# Looping_Louie_Motherboard.net
KiCad netlist of a schematic drawn in EAGLE
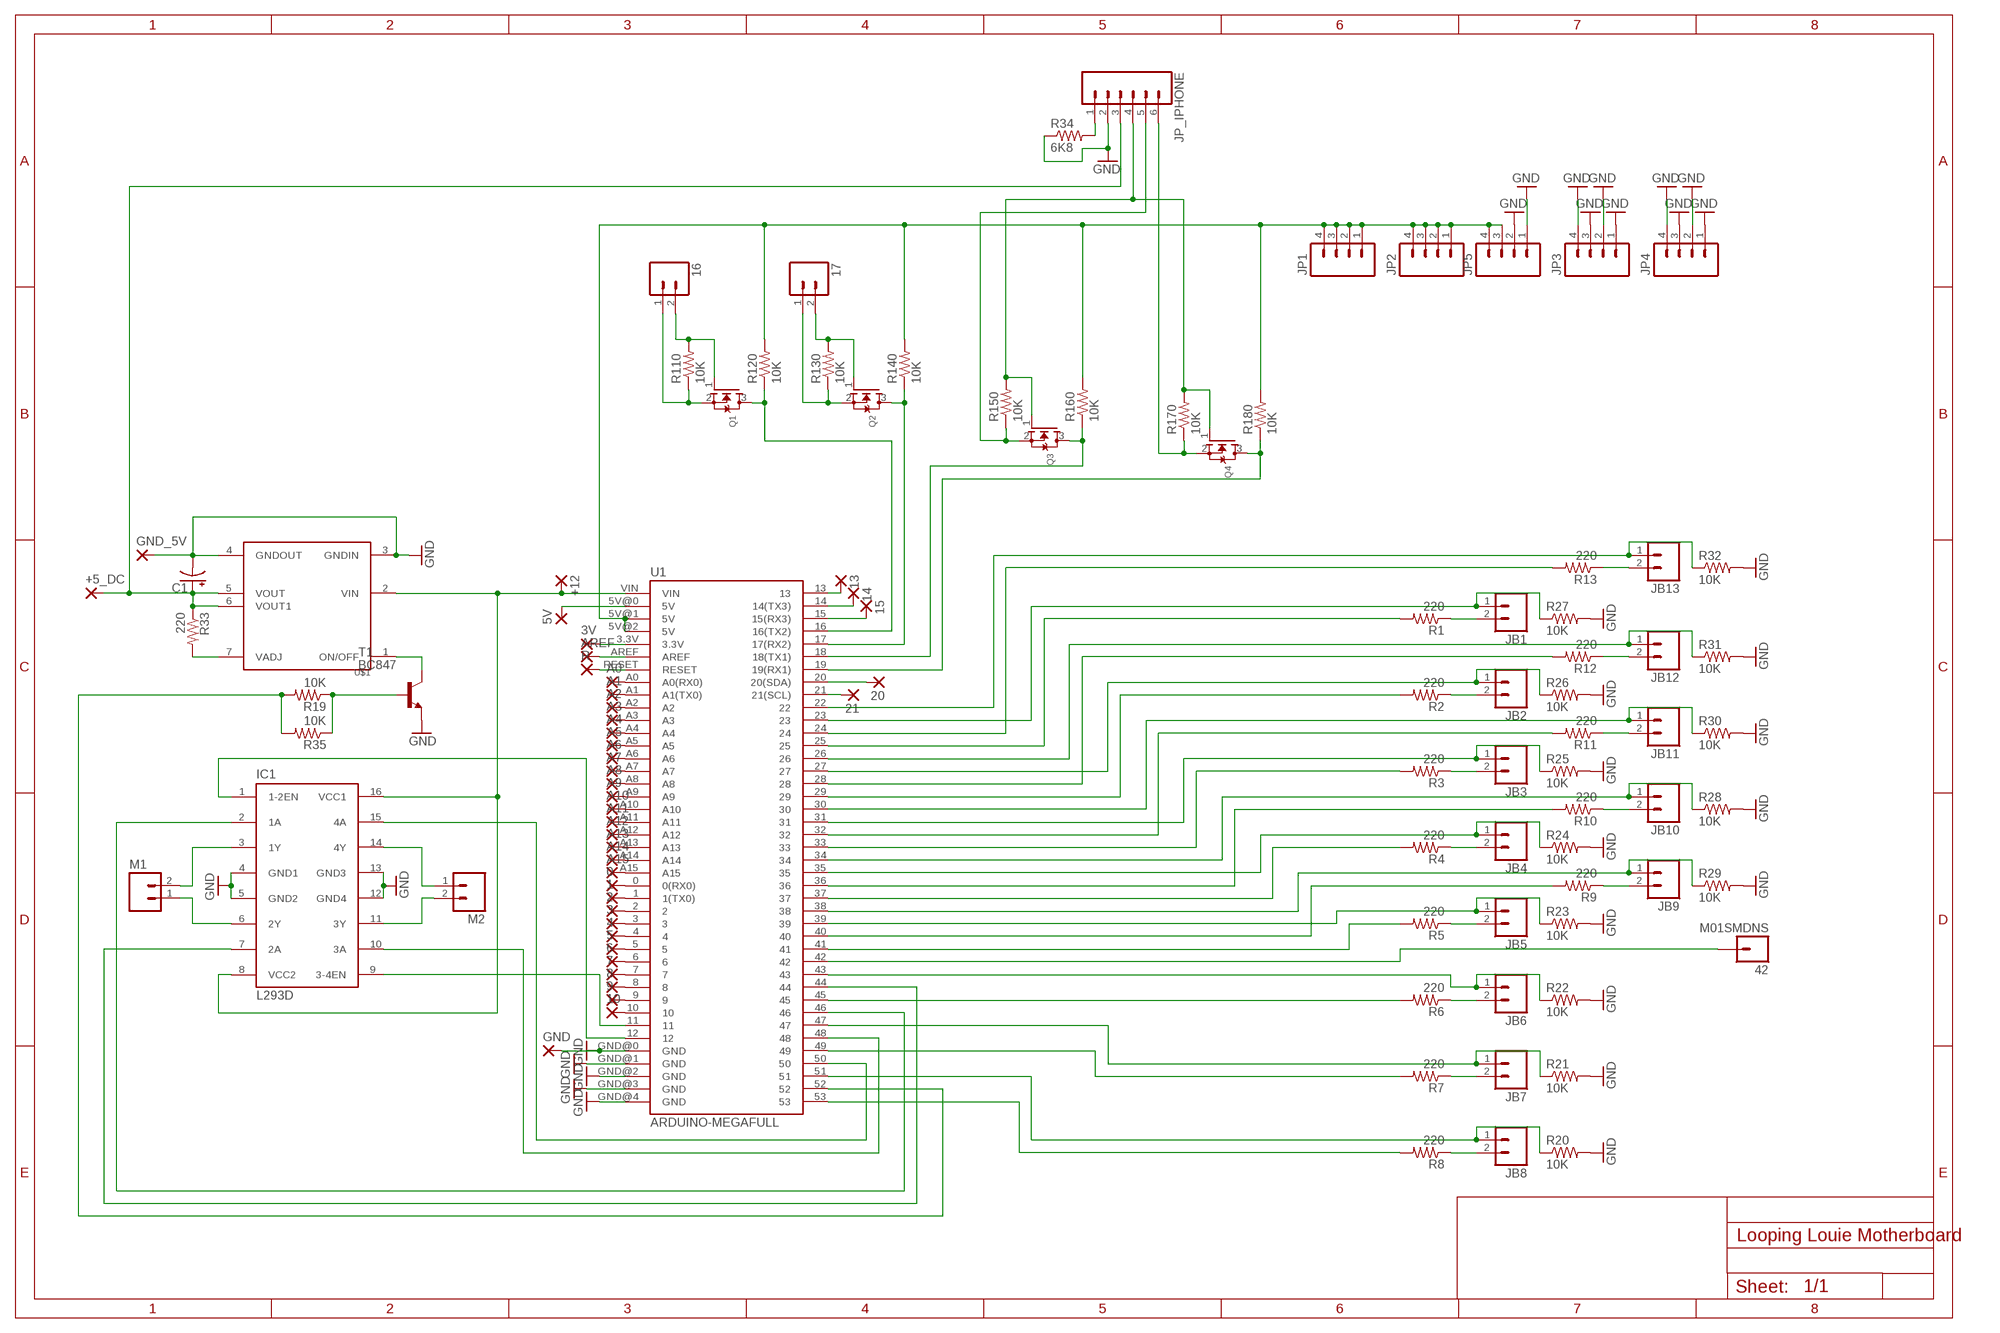
[diagram p0: schematic, sheet 1]

(export (version "E")
  (design (tool "Eeschema 10.0.6"))
  (components
    (comp (ref "+5_DC")
      (value "3,81/1,4")
      (footprint "eagle-import:3,81_1,4")
      (libsource (lib "eagle-import") (part "3,81/1,4"))
    )
    (comp (ref "+12")
      (value "3,81/1,4")
      (footprint "eagle-import:3,81_1,4")
      (libsource (lib "eagle-import") (part "3,81/1,4"))
    )
    (comp (ref "0")
      (value "1,6/0,8")
      (footprint "eagle-import:1,6_0,8")
      (libsource (lib "eagle-import") (part "1,6/0,8"))
    )
    (comp (ref "1")
      (value "1,6/0,8")
      (footprint "eagle-import:1,6_0,8")
      (libsource (lib "eagle-import") (part "1,6/0,8"))
    )
    (comp (ref "2")
      (value "1,6/0,8")
      (footprint "eagle-import:1,6_0,8")
      (libsource (lib "eagle-import") (part "1,6/0,8"))
    )
    (comp (ref "3")
      (value "1,6/0,8")
      (footprint "eagle-import:1,6_0,8")
      (libsource (lib "eagle-import") (part "1,6/0,8"))
    )
    (comp (ref "3V")
      (value "1,6/0,8")
      (footprint "eagle-import:1,6_0,8")
      (libsource (lib "eagle-import") (part "1,6/0,8"))
    )
    (comp (ref "4")
      (value "1,6/0,8")
      (footprint "eagle-import:1,6_0,8")
      (libsource (lib "eagle-import") (part "1,6/0,8"))
    )
    (comp (ref "5")
      (value "1,6/0,8")
      (footprint "eagle-import:1,6_0,8")
      (libsource (lib "eagle-import") (part "1,6/0,8"))
    )
    (comp (ref "5V")
      (value "1,6/0,8")
      (footprint "eagle-import:1,6_0,8")
      (libsource (lib "eagle-import") (part "1,6/0,8"))
    )
    (comp (ref "6")
      (value "1,6/0,8")
      (footprint "eagle-import:1,6_0,8")
      (libsource (lib "eagle-import") (part "1,6/0,8"))
    )
    (comp (ref "7")
      (value "1,6/0,8")
      (footprint "eagle-import:1,6_0,8")
      (libsource (lib "eagle-import") (part "1,6/0,8"))
    )
    (comp (ref "8")
      (value "1,6/0,8")
      (footprint "eagle-import:1,6_0,8")
      (libsource (lib "eagle-import") (part "1,6/0,8"))
    )
    (comp (ref "9")
      (value "1,6/0,8")
      (footprint "eagle-import:1,6_0,8")
      (libsource (lib "eagle-import") (part "1,6/0,8"))
    )
    (comp (ref "10")
      (value "1,6/0,8")
      (footprint "eagle-import:1,6_0,8")
      (libsource (lib "eagle-import") (part "1,6/0,8"))
    )
    (comp (ref "13")
      (value "1,6/0,8")
      (footprint "eagle-import:1,6_0,8")
      (libsource (lib "eagle-import") (part "1,6/0,8"))
    )
    (comp (ref "14")
      (value "1,6/0,8")
      (footprint "eagle-import:1,6_0,8")
      (libsource (lib "eagle-import") (part "1,6/0,8"))
    )
    (comp (ref "15")
      (value "1,6/0,8")
      (footprint "eagle-import:1,6_0,8")
      (libsource (lib "eagle-import") (part "1,6/0,8"))
    )
    (comp (ref "16")
      (value "M021X02_NO_SILK")
      (footprint "eagle-import:1X02_NO_SILK")
      (libsource (lib "eagle-import") (part "M021X02_NO_SILK"))
    )
    (comp (ref "17")
      (value "M021X02_NO_SILK")
      (footprint "eagle-import:1X02_NO_SILK")
      (libsource (lib "eagle-import") (part "M021X02_NO_SILK"))
    )
    (comp (ref "20")
      (value "1,6/0,8")
      (footprint "eagle-import:1,6_0,8")
      (libsource (lib "eagle-import") (part "1,6/0,8"))
    )
    (comp (ref "21")
      (value "1,6/0,8")
      (footprint "eagle-import:1,6_0,8")
      (libsource (lib "eagle-import") (part "1,6/0,8"))
    )
    (comp (ref "42")
      (value "M01SMDNS")
      (footprint "eagle-import:1X01NS")
      (libsource (lib "eagle-import") (part "M01SMDNS"))
    )
    (comp (ref "A0")
      (value "1,6/0,8")
      (footprint "eagle-import:1,6_0,8")
      (libsource (lib "eagle-import") (part "1,6/0,8"))
    )
    (comp (ref "A1")
      (value "1,6/0,8")
      (footprint "eagle-import:1,6_0,8")
      (libsource (lib "eagle-import") (part "1,6/0,8"))
    )
    (comp (ref "A2")
      (value "1,6/0,8")
      (footprint "eagle-import:1,6_0,8")
      (libsource (lib "eagle-import") (part "1,6/0,8"))
    )
    (comp (ref "A3")
      (value "1,6/0,8")
      (footprint "eagle-import:1,6_0,8")
      (libsource (lib "eagle-import") (part "1,6/0,8"))
    )
    (comp (ref "A4")
      (value "1,6/0,8")
      (footprint "eagle-import:1,6_0,8")
      (libsource (lib "eagle-import") (part "1,6/0,8"))
    )
    (comp (ref "A5")
      (value "1,6/0,8")
      (footprint "eagle-import:1,6_0,8")
      (libsource (lib "eagle-import") (part "1,6/0,8"))
    )
    (comp (ref "A6")
      (value "1,6/0,8")
      (footprint "eagle-import:1,6_0,8")
      (libsource (lib "eagle-import") (part "1,6/0,8"))
    )
    (comp (ref "A7")
      (value "1,6/0,8")
      (footprint "eagle-import:1,6_0,8")
      (libsource (lib "eagle-import") (part "1,6/0,8"))
    )
    (comp (ref "A8")
      (value "1,6/0,8")
      (footprint "eagle-import:1,6_0,8")
      (libsource (lib "eagle-import") (part "1,6/0,8"))
    )
    (comp (ref "A9")
      (value "1,6/0,8")
      (footprint "eagle-import:1,6_0,8")
      (libsource (lib "eagle-import") (part "1,6/0,8"))
    )
    (comp (ref "A10")
      (value "1,6/0,8")
      (footprint "eagle-import:1,6_0,8")
      (libsource (lib "eagle-import") (part "1,6/0,8"))
    )
    (comp (ref "A11")
      (value "1,6/0,8")
      (footprint "eagle-import:1,6_0,8")
      (libsource (lib "eagle-import") (part "1,6/0,8"))
    )
    (comp (ref "A12")
      (value "1,6/0,8")
      (footprint "eagle-import:1,6_0,8")
      (libsource (lib "eagle-import") (part "1,6/0,8"))
    )
    (comp (ref "A13")
      (value "1,6/0,8")
      (footprint "eagle-import:1,6_0,8")
      (libsource (lib "eagle-import") (part "1,6/0,8"))
    )
    (comp (ref "A14")
      (value "1,6/0,8")
      (footprint "eagle-import:1,6_0,8")
      (libsource (lib "eagle-import") (part "1,6/0,8"))
    )
    (comp (ref "A15")
      (value "1,6/0,8")
      (footprint "eagle-import:1,6_0,8")
      (libsource (lib "eagle-import") (part "1,6/0,8"))
    )
    (comp (ref "AREF")
      (value "1,6/0,8")
      (footprint "eagle-import:1,6_0,8")
      (libsource (lib "eagle-import") (part "1,6/0,8"))
    )
    (comp (ref "C1")
      (value "CAP_POLG")
      (footprint "eagle-import:PANASONIC_G")
      (libsource (lib "eagle-import") (part "CAP_POLG"))
    )
    (comp (ref "GND")
      (value "3,81/1,4")
      (footprint "eagle-import:3,81_1,4")
      (libsource (lib "eagle-import") (part "3,81/1,4"))
    )
    (comp (ref "GND_5V")
      (value "3,81/1,4")
      (footprint "eagle-import:3,81_1,4")
      (libsource (lib "eagle-import") (part "3,81/1,4"))
    )
    (comp (ref "IC1")
      (value "L293D")
      (footprint "eagle-import:DIL16")
      (libsource (lib "eagle-import") (part "L293D"))
    )
    (comp (ref "JB1")
      (value "M021X02_NO_SILK")
      (footprint "eagle-import:1X02_NO_SILK")
      (libsource (lib "eagle-import") (part "M021X02_NO_SILK"))
    )
    (comp (ref "JB2")
      (value "M021X02_NO_SILK")
      (footprint "eagle-import:1X02_NO_SILK")
      (libsource (lib "eagle-import") (part "M021X02_NO_SILK"))
    )
    (comp (ref "JB3")
      (value "M021X02_NO_SILK")
      (footprint "eagle-import:1X02_NO_SILK")
      (libsource (lib "eagle-import") (part "M021X02_NO_SILK"))
    )
    (comp (ref "JB4")
      (value "M021X02_NO_SILK")
      (footprint "eagle-import:1X02_NO_SILK")
      (libsource (lib "eagle-import") (part "M021X02_NO_SILK"))
    )
    (comp (ref "JB5")
      (value "M021X02_NO_SILK")
      (footprint "eagle-import:1X02_NO_SILK")
      (libsource (lib "eagle-import") (part "M021X02_NO_SILK"))
    )
    (comp (ref "JB6")
      (value "M021X02_NO_SILK")
      (footprint "eagle-import:1X02_NO_SILK")
      (libsource (lib "eagle-import") (part "M021X02_NO_SILK"))
    )
    (comp (ref "JB7")
      (value "M021X02_NO_SILK")
      (footprint "eagle-import:1X02_NO_SILK")
      (libsource (lib "eagle-import") (part "M021X02_NO_SILK"))
    )
    (comp (ref "JB8")
      (value "M021X02_NO_SILK")
      (footprint "eagle-import:1X02_NO_SILK")
      (libsource (lib "eagle-import") (part "M021X02_NO_SILK"))
    )
    (comp (ref "JB9")
      (value "M021X02_NO_SILK")
      (footprint "eagle-import:1X02_NO_SILK")
      (libsource (lib "eagle-import") (part "M021X02_NO_SILK"))
    )
    (comp (ref "JB10")
      (value "M021X02_NO_SILK")
      (footprint "eagle-import:1X02_NO_SILK")
      (libsource (lib "eagle-import") (part "M021X02_NO_SILK"))
    )
    (comp (ref "JB11")
      (value "M021X02_NO_SILK")
      (footprint "eagle-import:1X02_NO_SILK")
      (libsource (lib "eagle-import") (part "M021X02_NO_SILK"))
    )
    (comp (ref "JB12")
      (value "M021X02_NO_SILK")
      (footprint "eagle-import:1X02_NO_SILK")
      (libsource (lib "eagle-import") (part "M021X02_NO_SILK"))
    )
    (comp (ref "JB13")
      (value "M021X02_NO_SILK")
      (footprint "eagle-import:1X02_NO_SILK")
      (libsource (lib "eagle-import") (part "M021X02_NO_SILK"))
    )
    (comp (ref "JP1")
      (value "M041X04_NO_SILK")
      (footprint "eagle-import:1X04_NO_SILK")
      (libsource (lib "eagle-import") (part "M041X04_NO_SILK"))
    )
    (comp (ref "JP2")
      (value "M041X04_NO_SILK")
      (footprint "eagle-import:1X04_NO_SILK")
      (libsource (lib "eagle-import") (part "M041X04_NO_SILK"))
    )
    (comp (ref "JP3")
      (value "M041X04_NO_SILK")
      (footprint "eagle-import:1X04_NO_SILK")
      (libsource (lib "eagle-import") (part "M041X04_NO_SILK"))
    )
    (comp (ref "JP4")
      (value "M041X04_NO_SILK")
      (footprint "eagle-import:1X04_NO_SILK")
      (libsource (lib "eagle-import") (part "M041X04_NO_SILK"))
    )
    (comp (ref "JP5")
      (value "M041X04_NO_SILK")
      (footprint "eagle-import:1X04_NO_SILK")
      (libsource (lib "eagle-import") (part "M041X04_NO_SILK"))
    )
    (comp (ref "JP_IPHONE")
      (value "M06LONGPADS")
      (footprint "eagle-import:1X06_LONGPADS")
      (libsource (lib "eagle-import") (part "M06LONGPADS"))
    )
    (comp (ref "M1")
      (value "M02PTH3")
      (footprint "eagle-import:1X02_LONGPADS")
      (libsource (lib "eagle-import") (part "M02PTH3"))
    )
    (comp (ref "M2")
      (value "M02PTH3")
      (footprint "eagle-import:1X02_LONGPADS")
      (libsource (lib "eagle-import") (part "M02PTH3"))
    )
    (comp (ref "Q1")
      (value "MOSFET-NWAVE")
      (footprint "eagle-import:SOT23-W")
      (libsource (lib "eagle-import") (part "MOSFET-NWAVE"))
    )
    (comp (ref "Q2")
      (value "MOSFET-NWAVE")
      (footprint "eagle-import:SOT23-W")
      (libsource (lib "eagle-import") (part "MOSFET-NWAVE"))
    )
    (comp (ref "Q3")
      (value "MOSFET-NWAVE")
      (footprint "eagle-import:SOT23-W")
      (libsource (lib "eagle-import") (part "MOSFET-NWAVE"))
    )
    (comp (ref "Q4")
      (value "MOSFET-NWAVE")
      (footprint "eagle-import:SOT23-W")
      (libsource (lib "eagle-import") (part "MOSFET-NWAVE"))
    )
    (comp (ref "R")
      (value "1,6/0,8")
      (footprint "eagle-import:1,6_0,8")
      (libsource (lib "eagle-import") (part "1,6/0,8"))
    )
    (comp (ref "R1")
      (value "220")
      (footprint "eagle-import:0603-RES")
      (libsource (lib "eagle-import") (part "RESISTOR0603-RES"))
    )
    (comp (ref "R2")
      (value "220")
      (footprint "eagle-import:0603-RES")
      (libsource (lib "eagle-import") (part "RESISTOR0603-RES"))
    )
    (comp (ref "R3")
      (value "220")
      (footprint "eagle-import:0603-RES")
      (libsource (lib "eagle-import") (part "RESISTOR0603-RES"))
    )
    (comp (ref "R4")
      (value "220")
      (footprint "eagle-import:0603-RES")
      (libsource (lib "eagle-import") (part "RESISTOR0603-RES"))
    )
    (comp (ref "R5")
      (value "220")
      (footprint "eagle-import:0603-RES")
      (libsource (lib "eagle-import") (part "RESISTOR0603-RES"))
    )
    (comp (ref "R6")
      (value "220")
      (footprint "eagle-import:0603-RES")
      (libsource (lib "eagle-import") (part "RESISTOR0603-RES"))
    )
    (comp (ref "R7")
      (value "220")
      (footprint "eagle-import:0603-RES")
      (libsource (lib "eagle-import") (part "RESISTOR0603-RES"))
    )
    (comp (ref "R8")
      (value "220")
      (footprint "eagle-import:0603-RES")
      (libsource (lib "eagle-import") (part "RESISTOR0603-RES"))
    )
    (comp (ref "R9")
      (value "220")
      (footprint "eagle-import:0603-RES")
      (libsource (lib "eagle-import") (part "RESISTOR0603-RES"))
    )
    (comp (ref "R10")
      (value "220")
      (footprint "eagle-import:0603-RES")
      (libsource (lib "eagle-import") (part "RESISTOR0603-RES"))
    )
    (comp (ref "R11")
      (value "220")
      (footprint "eagle-import:0603-RES")
      (libsource (lib "eagle-import") (part "RESISTOR0603-RES"))
    )
    (comp (ref "R12")
      (value "220")
      (footprint "eagle-import:0603-RES")
      (libsource (lib "eagle-import") (part "RESISTOR0603-RES"))
    )
    (comp (ref "R13")
      (value "220")
      (footprint "eagle-import:0603-RES")
      (libsource (lib "eagle-import") (part "RESISTOR0603-RES"))
    )
    (comp (ref "R19")
      (value "10K")
      (footprint "eagle-import:0603-RES")
      (libsource (lib "eagle-import") (part "RESISTOR0603-RES"))
    )
    (comp (ref "R20")
      (value "10K")
      (footprint "eagle-import:0603-RES")
      (libsource (lib "eagle-import") (part "RESISTOR0603-RES"))
    )
    (comp (ref "R21")
      (value "10K")
      (footprint "eagle-import:0603-RES")
      (libsource (lib "eagle-import") (part "RESISTOR0603-RES"))
    )
    (comp (ref "R22")
      (value "10K")
      (footprint "eagle-import:0603-RES")
      (libsource (lib "eagle-import") (part "RESISTOR0603-RES"))
    )
    (comp (ref "R23")
      (value "10K")
      (footprint "eagle-import:0603-RES")
      (libsource (lib "eagle-import") (part "RESISTOR0603-RES"))
    )
    (comp (ref "R24")
      (value "10K")
      (footprint "eagle-import:0603-RES")
      (libsource (lib "eagle-import") (part "RESISTOR0603-RES"))
    )
    (comp (ref "R25")
      (value "10K")
      (footprint "eagle-import:0603-RES")
      (libsource (lib "eagle-import") (part "RESISTOR0603-RES"))
    )
    (comp (ref "R26")
      (value "10K")
      (footprint "eagle-import:0603-RES")
      (libsource (lib "eagle-import") (part "RESISTOR0603-RES"))
    )
    (comp (ref "R27")
      (value "10K")
      (footprint "eagle-import:0603-RES")
      (libsource (lib "eagle-import") (part "RESISTOR0603-RES"))
    )
    (comp (ref "R28")
      (value "10K")
      (footprint "eagle-import:0603-RES")
      (libsource (lib "eagle-import") (part "RESISTOR0603-RES"))
    )
    (comp (ref "R29")
      (value "10K")
      (footprint "eagle-import:0603-RES")
      (libsource (lib "eagle-import") (part "RESISTOR0603-RES"))
    )
    (comp (ref "R30")
      (value "10K")
      (footprint "eagle-import:0603-RES")
      (libsource (lib "eagle-import") (part "RESISTOR0603-RES"))
    )
    (comp (ref "R31")
      (value "10K")
      (footprint "eagle-import:0603-RES")
      (libsource (lib "eagle-import") (part "RESISTOR0603-RES"))
    )
    (comp (ref "R32")
      (value "10K")
      (footprint "eagle-import:0603-RES")
      (libsource (lib "eagle-import") (part "RESISTOR0603-RES"))
    )
    (comp (ref "R33")
      (value "220")
      (footprint "eagle-import:0603-RES")
      (libsource (lib "eagle-import") (part "RESISTOR0603-RES"))
    )
    (comp (ref "R34")
      (value "6K8")
      (footprint "eagle-import:0603-RES")
      (libsource (lib "eagle-import") (part "RESISTOR0603-RES"))
    )
    (comp (ref "R35")
      (value "10K")
      (footprint "eagle-import:0603-RES")
      (libsource (lib "eagle-import") (part "RESISTOR0603-RES"))
    )
    (comp (ref "R110")
      (value "10K")
      (footprint "eagle-import:0603-RES")
      (libsource (lib "eagle-import") (part "RESISTOR0603-RES"))
    )
    (comp (ref "R120")
      (value "10K")
      (footprint "eagle-import:0603-RES")
      (libsource (lib "eagle-import") (part "RESISTOR0603-RES"))
    )
    (comp (ref "R130")
      (value "10K")
      (footprint "eagle-import:0603-RES")
      (libsource (lib "eagle-import") (part "RESISTOR0603-RES"))
    )
    (comp (ref "R140")
      (value "10K")
      (footprint "eagle-import:0603-RES")
      (libsource (lib "eagle-import") (part "RESISTOR0603-RES"))
    )
    (comp (ref "R150")
      (value "10K")
      (footprint "eagle-import:0603-RES")
      (libsource (lib "eagle-import") (part "RESISTOR0603-RES"))
    )
    (comp (ref "R160")
      (value "10K")
      (footprint "eagle-import:0603-RES")
      (libsource (lib "eagle-import") (part "RESISTOR0603-RES"))
    )
    (comp (ref "R170")
      (value "10K")
      (footprint "eagle-import:0603-RES")
      (libsource (lib "eagle-import") (part "RESISTOR0603-RES"))
    )
    (comp (ref "R180")
      (value "10K")
      (footprint "eagle-import:0603-RES")
      (libsource (lib "eagle-import") (part "RESISTOR0603-RES"))
    )
    (comp (ref "T1")
      (value "BC847")
      (footprint "eagle-import:SOT23")
      (libsource (lib "eagle-import") (part "BC847"))
    )
    (comp (ref "U$1")
      (value "KIS-3R33S")
      (footprint "eagle-import:KIS-3R33S")
      (libsource (lib "eagle-import") (part "KIS-3R33S"))
    )
    (comp (ref "U1")
      (value "ARDUINO-MEGAFULL")
      (footprint "eagle-import:ARDUINO_MEGA_MIRROR")
      (libsource (lib "eagle-import") (part "ARDUINO-MEGAFULL"))
    )
  )
  (nets
    (net (code "1") (name "GND") (class "Default")
      (node (ref "C1") (pin "-") (pinfunction "-_-") (pintype "passive"))
      (node (ref "GND") (pin "1") (pinfunction "P_1") (pintype "passive"))
      (node (ref "GND_5V") (pin "1") (pinfunction "P_1") (pintype "passive"))
      (node (ref "IC1") (pin "12") (pinfunction "GND4_12") (pintype "power_in"))
      (node (ref "IC1") (pin "13") (pinfunction "GND3_13") (pintype "power_in"))
      (node (ref "IC1") (pin "4") (pinfunction "GND1_4") (pintype "power_in"))
      (node (ref "IC1") (pin "5") (pinfunction "GND2_5") (pintype "power_in"))
      (node (ref "JP3") (pin "1") (pinfunction "1_1") (pintype "passive"))
      (node (ref "JP3") (pin "2") (pinfunction "2_2") (pintype "passive"))
      (node (ref "JP3") (pin "3") (pinfunction "3_3") (pintype "passive"))
      (node (ref "JP3") (pin "4") (pinfunction "4_4") (pintype "passive"))
      (node (ref "JP4") (pin "1") (pinfunction "1_1") (pintype "passive"))
      (node (ref "JP4") (pin "2") (pinfunction "2_2") (pintype "passive"))
      (node (ref "JP4") (pin "3") (pinfunction "3_3") (pintype "passive"))
      (node (ref "JP4") (pin "4") (pinfunction "4_4") (pintype "passive"))
      (node (ref "JP5") (pin "1") (pinfunction "1_1") (pintype "passive"))
      (node (ref "JP5") (pin "2") (pinfunction "2_2") (pintype "passive"))
      (node (ref "JP_IPHONE") (pin "2") (pinfunction "2_2") (pintype "passive"))
      (node (ref "R20") (pin "2") (pinfunction "2_2") (pintype "passive"))
      (node (ref "R21") (pin "2") (pinfunction "2_2") (pintype "passive"))
      (node (ref "R22") (pin "2") (pinfunction "2_2") (pintype "passive"))
      (node (ref "R23") (pin "2") (pinfunction "2_2") (pintype "passive"))
      (node (ref "R24") (pin "2") (pinfunction "2_2") (pintype "passive"))
      (node (ref "R25") (pin "2") (pinfunction "2_2") (pintype "passive"))
      (node (ref "R26") (pin "2") (pinfunction "2_2") (pintype "passive"))
      (node (ref "R27") (pin "2") (pinfunction "2_2") (pintype "passive"))
      (node (ref "R28") (pin "2") (pinfunction "2_2") (pintype "passive"))
      (node (ref "R29") (pin "2") (pinfunction "2_2") (pintype "passive"))
      (node (ref "R30") (pin "2") (pinfunction "2_2") (pintype "passive"))
      (node (ref "R31") (pin "2") (pinfunction "2_2") (pintype "passive"))
      (node (ref "R32") (pin "2") (pinfunction "2_2") (pintype "passive"))
      (node (ref "R34") (pin "1") (pinfunction "1_1") (pintype "passive"))
      (node (ref "T1") (pin "2") (pinfunction "E_2") (pintype "passive"))
      (node (ref "U$1") (pin "3") (pinfunction "GNDIN_3") (pintype "power_in"))
      (node (ref "U$1") (pin "4") (pinfunction "GNDOUT_4") (pintype "power_in"))
      (node (ref "U1") (pin "GND@0") (pinfunction "GND_GND@0") (pintype "bidirectional"))
      (node (ref "U1") (pin "GND@1") (pinfunction "GND_GND@1") (pintype "bidirectional"))
      (node (ref "U1") (pin "GND@2") (pinfunction "GND_GND@2") (pintype "bidirectional"))
      (node (ref "U1") (pin "GND@3") (pinfunction "GND_GND@3") (pintype "bidirectional"))
      (node (ref "U1") (pin "GND@4") (pinfunction "GND_GND@4") (pintype "bidirectional"))
    )
    (net (code "2") (name "Net-(+5_DC-P)") (class "Default")
      (node (ref "+5_DC") (pin "1") (pinfunction "P_1") (pintype "passive"))
      (node (ref "C1") (pin "+") (pinfunction "+_+") (pintype "passive"))
      (node (ref "JP_IPHONE") (pin "3") (pinfunction "3_3") (pintype "passive"))
      (node (ref "R33") (pin "1") (pinfunction "1_1") (pintype "passive"))
      (node (ref "U$1") (pin "5") (pinfunction "VOUT_5") (pintype "bidirectional"))
      (node (ref "U$1") (pin "6") (pinfunction "VOUT1_6") (pintype "bidirectional"))
    )
    (net (code "3") (name "Net-(+12-P)") (class "Default")
      (node (ref "+12") (pin "1") (pinfunction "P_1") (pintype "passive"))
      (node (ref "IC1") (pin "16") (pinfunction "VCC1_16") (pintype "power_in"))
      (node (ref "IC1") (pin "8") (pinfunction "VCC2_8") (pintype "power_in"))
      (node (ref "U$1") (pin "2") (pinfunction "VIN_2") (pintype "bidirectional"))
      (node (ref "U1") (pin "VIN") (pinfunction "VIN_VIN") (pintype "bidirectional"))
    )
    (net (code "4") (name "Net-(0-P)") (class "Default")
      (node (ref "0") (pin "1") (pinfunction "P_1") (pintype "passive"))
      (node (ref "U1") (pin "0") (pinfunction "0(RX0)_0") (pintype "bidirectional"))
    )
    (net (code "5") (name "Net-(1-P)") (class "Default")
      (node (ref "1") (pin "1") (pinfunction "P_1") (pintype "passive"))
      (node (ref "U1") (pin "1") (pinfunction "1(TX0)_1") (pintype "bidirectional"))
    )
    (net (code "6") (name "Net-(2-P)") (class "Default")
      (node (ref "2") (pin "1") (pinfunction "P_1") (pintype "passive"))
      (node (ref "U1") (pin "2") (pinfunction "2_2") (pintype "bidirectional"))
    )
    (net (code "7") (name "Net-(3-P)") (class "Default")
      (node (ref "3") (pin "1") (pinfunction "P_1") (pintype "passive"))
      (node (ref "U1") (pin "3") (pinfunction "3_3") (pintype "bidirectional"))
    )
    (net (code "8") (name "Net-(3V-P)") (class "Default")
      (node (ref "3V") (pin "1") (pinfunction "P_1") (pintype "passive"))
      (node (ref "U1") (pin "3.3V") (pinfunction "3.3V_3.3V") (pintype "bidirectional"))
    )
    (net (code "9") (name "Net-(4-P)") (class "Default")
      (node (ref "4") (pin "1") (pinfunction "P_1") (pintype "passive"))
      (node (ref "U1") (pin "4") (pinfunction "4_4") (pintype "bidirectional"))
    )
    (net (code "10") (name "Net-(5-P)") (class "Default")
      (node (ref "5") (pin "1") (pinfunction "P_1") (pintype "passive"))
      (node (ref "U1") (pin "5") (pinfunction "5_5") (pintype "bidirectional"))
    )
    (net (code "11") (name "Net-(5V-P)") (class "Default")
      (node (ref "5V") (pin "1") (pinfunction "P_1") (pintype "passive"))
      (node (ref "U1") (pin "5V@0") (pinfunction "5V_5V@0") (pintype "bidirectional"))
    )
    (net (code "12") (name "Net-(6-P)") (class "Default")
      (node (ref "6") (pin "1") (pinfunction "P_1") (pintype "passive"))
      (node (ref "U1") (pin "6") (pinfunction "6_6") (pintype "bidirectional"))
    )
    (net (code "13") (name "Net-(7-P)") (class "Default")
      (node (ref "7") (pin "1") (pinfunction "P_1") (pintype "passive"))
      (node (ref "U1") (pin "7") (pinfunction "7_7") (pintype "bidirectional"))
    )
    (net (code "14") (name "Net-(8-P)") (class "Default")
      (node (ref "8") (pin "1") (pinfunction "P_1") (pintype "passive"))
      (node (ref "U1") (pin "8") (pinfunction "8_8") (pintype "bidirectional"))
    )
    (net (code "15") (name "Net-(9-P)") (class "Default")
      (node (ref "9") (pin "1") (pinfunction "P_1") (pintype "passive"))
      (node (ref "U1") (pin "9") (pinfunction "9_9") (pintype "bidirectional"))
    )
    (net (code "16") (name "Net-(10-P)") (class "Default")
      (node (ref "10") (pin "1") (pinfunction "P_1") (pintype "passive"))
      (node (ref "U1") (pin "10") (pinfunction "10_10") (pintype "bidirectional"))
    )
    (net (code "17") (name "Net-(13-P)") (class "Default")
      (node (ref "13") (pin "1") (pinfunction "P_1") (pintype "passive"))
      (node (ref "U1") (pin "13") (pinfunction "13_13") (pintype "bidirectional"))
    )
    (net (code "18") (name "Net-(14-P)") (class "Default")
      (node (ref "14") (pin "1") (pinfunction "P_1") (pintype "passive"))
      (node (ref "U1") (pin "14") (pinfunction "14(TX3)_14") (pintype "bidirectional"))
    )
    (net (code "19") (name "Net-(15-P)") (class "Default")
      (node (ref "15") (pin "1") (pinfunction "P_1") (pintype "passive"))
      (node (ref "U1") (pin "15") (pinfunction "15(RX3)_15") (pintype "bidirectional"))
    )
    (net (code "20") (name "Net-(20-P)") (class "Default")
      (node (ref "20") (pin "1") (pinfunction "P_1") (pintype "passive"))
      (node (ref "U1") (pin "20") (pinfunction "20(SDA)_20") (pintype "bidirectional"))
    )
    (net (code "21") (name "Net-(21-P)") (class "Default")
      (node (ref "21") (pin "1") (pinfunction "P_1") (pintype "passive"))
      (node (ref "U1") (pin "21") (pinfunction "21(SCL)_21") (pintype "bidirectional"))
    )
    (net (code "22") (name "Net-(42-Pad1)") (class "Default")
      (node (ref "42") (pin "1") (pinfunction "1_1") (pintype "passive"))
      (node (ref "U1") (pin "42") (pinfunction "42_42") (pintype "bidirectional"))
    )
    (net (code "23") (name "Net-(A0-P)") (class "Default")
      (node (ref "A0") (pin "1") (pinfunction "P_1") (pintype "passive"))
      (node (ref "U1") (pin "A0") (pinfunction "A0(RX0)_A0") (pintype "bidirectional"))
    )
    (net (code "24") (name "Net-(A1-P)") (class "Default")
      (node (ref "A1") (pin "1") (pinfunction "P_1") (pintype "passive"))
      (node (ref "U1") (pin "A1") (pinfunction "A1(TX0)_A1") (pintype "bidirectional"))
    )
    (net (code "25") (name "Net-(A2-P)") (class "Default")
      (node (ref "A2") (pin "1") (pinfunction "P_1") (pintype "passive"))
      (node (ref "U1") (pin "A2") (pinfunction "A2_A2") (pintype "bidirectional"))
    )
    (net (code "26") (name "Net-(A3-P)") (class "Default")
      (node (ref "A3") (pin "1") (pinfunction "P_1") (pintype "passive"))
      (node (ref "U1") (pin "A3") (pinfunction "A3_A3") (pintype "bidirectional"))
    )
    (net (code "27") (name "Net-(A4-P)") (class "Default")
      (node (ref "A4") (pin "1") (pinfunction "P_1") (pintype "passive"))
      (node (ref "U1") (pin "A4") (pinfunction "A4_A4") (pintype "bidirectional"))
    )
    (net (code "28") (name "Net-(A5-P)") (class "Default")
      (node (ref "A5") (pin "1") (pinfunction "P_1") (pintype "passive"))
      (node (ref "U1") (pin "A5") (pinfunction "A5_A5") (pintype "bidirectional"))
    )
    (net (code "29") (name "Net-(A6-P)") (class "Default")
      (node (ref "A6") (pin "1") (pinfunction "P_1") (pintype "passive"))
      (node (ref "U1") (pin "A6") (pinfunction "A6_A6") (pintype "bidirectional"))
    )
    (net (code "30") (name "Net-(A7-P)") (class "Default")
      (node (ref "A7") (pin "1") (pinfunction "P_1") (pintype "passive"))
      (node (ref "U1") (pin "A7") (pinfunction "A7_A7") (pintype "bidirectional"))
    )
    (net (code "31") (name "Net-(A8-P)") (class "Default")
      (node (ref "A8") (pin "1") (pinfunction "P_1") (pintype "passive"))
      (node (ref "U1") (pin "A8") (pinfunction "A8_A8") (pintype "bidirectional"))
    )
    (net (code "32") (name "Net-(A9-P)") (class "Default")
      (node (ref "A9") (pin "1") (pinfunction "P_1") (pintype "passive"))
      (node (ref "U1") (pin "A9") (pinfunction "A9_A9") (pintype "bidirectional"))
    )
    (net (code "33") (name "Net-(A10-P)") (class "Default")
      (node (ref "A10") (pin "1") (pinfunction "P_1") (pintype "passive"))
      (node (ref "U1") (pin "A10") (pinfunction "A10_A10") (pintype "bidirectional"))
    )
    (net (code "34") (name "Net-(A11-P)") (class "Default")
      (node (ref "A11") (pin "1") (pinfunction "P_1") (pintype "passive"))
      (node (ref "U1") (pin "A11") (pinfunction "A11_A11") (pintype "bidirectional"))
    )
    (net (code "35") (name "Net-(A12-P)") (class "Default")
      (node (ref "A12") (pin "1") (pinfunction "P_1") (pintype "passive"))
      (node (ref "U1") (pin "A12") (pinfunction "A12_A12") (pintype "bidirectional"))
    )
    (net (code "36") (name "Net-(A13-P)") (class "Default")
      (node (ref "A13") (pin "1") (pinfunction "P_1") (pintype "passive"))
      (node (ref "U1") (pin "A13") (pinfunction "A13_A13") (pintype "bidirectional"))
    )
    (net (code "37") (name "Net-(A14-P)") (class "Default")
      (node (ref "A14") (pin "1") (pinfunction "P_1") (pintype "passive"))
      (node (ref "U1") (pin "A14") (pinfunction "A14_A14") (pintype "bidirectional"))
    )
    (net (code "38") (name "Net-(A15-P)") (class "Default")
      (node (ref "A15") (pin "1") (pinfunction "P_1") (pintype "passive"))
      (node (ref "U1") (pin "A15") (pinfunction "A15_A15") (pintype "bidirectional"))
    )
    (net (code "39") (name "Net-(AREF-P)") (class "Default")
      (node (ref "AREF") (pin "1") (pinfunction "P_1") (pintype "passive"))
      (node (ref "U1") (pin "AREF") (pinfunction "AREF_AREF") (pintype "bidirectional"))
    )
    (net (code "40") (name "Net-(IC1-1-2EN)") (class "Default")
      (node (ref "IC1") (pin "1") (pinfunction "1-2EN_1") (pintype "input"))
      (node (ref "U1") (pin "12") (pinfunction "12_12") (pintype "bidirectional"))
    )
    (net (code "41") (name "Net-(IC1-1A)") (class "Default")
      (node (ref "IC1") (pin "2") (pinfunction "1A_2") (pintype "input"))
      (node (ref "U1") (pin "46") (pinfunction "46_46") (pintype "bidirectional"))
    )
    (net (code "42") (name "Net-(IC1-1Y)") (class "Default")
      (node (ref "IC1") (pin "3") (pinfunction "1Y_3") (pintype "output"))
      (node (ref "M1") (pin "2") (pinfunction "2_2") (pintype "passive"))
    )
    (net (code "43") (name "Net-(IC1-2A)") (class "Default")
      (node (ref "IC1") (pin "7") (pinfunction "2A_7") (pintype "input"))
      (node (ref "U1") (pin "44") (pinfunction "44_44") (pintype "bidirectional"))
    )
    (net (code "44") (name "Net-(IC1-2Y)") (class "Default")
      (node (ref "IC1") (pin "6") (pinfunction "2Y_6") (pintype "output"))
      (node (ref "M1") (pin "1") (pinfunction "1_1") (pintype "passive"))
    )
    (net (code "45") (name "Net-(IC1-3-4EN)") (class "Default")
      (node (ref "IC1") (pin "9") (pinfunction "3-4EN_9") (pintype "input"))
      (node (ref "U1") (pin "11") (pinfunction "11_11") (pintype "bidirectional"))
    )
    (net (code "46") (name "Net-(IC1-3A)") (class "Default")
      (node (ref "IC1") (pin "10") (pinfunction "3A_10") (pintype "input"))
      (node (ref "U1") (pin "48") (pinfunction "48_48") (pintype "bidirectional"))
    )
    (net (code "47") (name "Net-(IC1-3Y)") (class "Default")
      (node (ref "IC1") (pin "11") (pinfunction "3Y_11") (pintype "output"))
      (node (ref "M2") (pin "2") (pinfunction "2_2") (pintype "passive"))
    )
    (net (code "48") (name "Net-(IC1-4A)") (class "Default")
      (node (ref "IC1") (pin "15") (pinfunction "4A_15") (pintype "input"))
      (node (ref "U1") (pin "50") (pinfunction "50_50") (pintype "bidirectional"))
    )
    (net (code "49") (name "Net-(IC1-4Y)") (class "Default")
      (node (ref "IC1") (pin "14") (pinfunction "4Y_14") (pintype "output"))
      (node (ref "M2") (pin "1") (pinfunction "1_1") (pintype "passive"))
    )
    (net (code "50") (name "Net-(JB1-Pad1)") (class "Default")
      (node (ref "JB1") (pin "1") (pinfunction "1_1") (pintype "passive"))
      (node (ref "R27") (pin "1") (pinfunction "1_1") (pintype "passive"))
      (node (ref "U1") (pin "23") (pinfunction "23_23") (pintype "bidirectional"))
    )
    (net (code "51") (name "Net-(JB1-Pad2)") (class "Default")
      (node (ref "JB1") (pin "2") (pinfunction "2_2") (pintype "passive"))
      (node (ref "R1") (pin "1") (pinfunction "1_1") (pintype "passive"))
    )
    (net (code "52") (name "Net-(JB2-Pad1)") (class "Default")
      (node (ref "JB2") (pin "1") (pinfunction "1_1") (pintype "passive"))
      (node (ref "R26") (pin "1") (pinfunction "1_1") (pintype "passive"))
      (node (ref "U1") (pin "27") (pinfunction "27_27") (pintype "bidirectional"))
    )
    (net (code "53") (name "Net-(JB2-Pad2)") (class "Default")
      (node (ref "JB2") (pin "2") (pinfunction "2_2") (pintype "passive"))
      (node (ref "R2") (pin "1") (pinfunction "1_1") (pintype "passive"))
    )
    (net (code "54") (name "Net-(JB3-Pad1)") (class "Default")
      (node (ref "JB3") (pin "1") (pinfunction "1_1") (pintype "passive"))
      (node (ref "R25") (pin "1") (pinfunction "1_1") (pintype "passive"))
      (node (ref "U1") (pin "31") (pinfunction "31_31") (pintype "bidirectional"))
    )
    (net (code "55") (name "Net-(JB3-Pad2)") (class "Default")
      (node (ref "JB3") (pin "2") (pinfunction "2_2") (pintype "passive"))
      (node (ref "R3") (pin "1") (pinfunction "1_1") (pintype "passive"))
    )
    (net (code "56") (name "Net-(JB4-Pad1)") (class "Default")
      (node (ref "JB4") (pin "1") (pinfunction "1_1") (pintype "passive"))
      (node (ref "R24") (pin "1") (pinfunction "1_1") (pintype "passive"))
      (node (ref "U1") (pin "35") (pinfunction "35_35") (pintype "bidirectional"))
    )
    (net (code "57") (name "Net-(JB4-Pad2)") (class "Default")
      (node (ref "JB4") (pin "2") (pinfunction "2_2") (pintype "passive"))
      (node (ref "R4") (pin "1") (pinfunction "1_1") (pintype "passive"))
    )
    (net (code "58") (name "Net-(JB5-Pad1)") (class "Default")
      (node (ref "JB5") (pin "1") (pinfunction "1_1") (pintype "passive"))
      (node (ref "R23") (pin "1") (pinfunction "1_1") (pintype "passive"))
      (node (ref "U1") (pin "39") (pinfunction "39_39") (pintype "bidirectional"))
    )
    (net (code "59") (name "Net-(JB5-Pad2)") (class "Default")
      (node (ref "JB5") (pin "2") (pinfunction "2_2") (pintype "passive"))
      (node (ref "R5") (pin "1") (pinfunction "1_1") (pintype "passive"))
    )
    (net (code "60") (name "Net-(JB6-Pad1)") (class "Default")
      (node (ref "JB6") (pin "1") (pinfunction "1_1") (pintype "passive"))
      (node (ref "R22") (pin "1") (pinfunction "1_1") (pintype "passive"))
      (node (ref "U1") (pin "43") (pinfunction "43_43") (pintype "bidirectional"))
    )
    (net (code "61") (name "Net-(JB6-Pad2)") (class "Default")
      (node (ref "JB6") (pin "2") (pinfunction "2_2") (pintype "passive"))
      (node (ref "R6") (pin "1") (pinfunction "1_1") (pintype "passive"))
    )
    (net (code "62") (name "Net-(JB7-Pad1)") (class "Default")
      (node (ref "JB7") (pin "1") (pinfunction "1_1") (pintype "passive"))
      (node (ref "R21") (pin "1") (pinfunction "1_1") (pintype "passive"))
      (node (ref "U1") (pin "47") (pinfunction "47_47") (pintype "bidirectional"))
    )
    (net (code "63") (name "Net-(JB7-Pad2)") (class "Default")
      (node (ref "JB7") (pin "2") (pinfunction "2_2") (pintype "passive"))
      (node (ref "R7") (pin "1") (pinfunction "1_1") (pintype "passive"))
    )
    (net (code "64") (name "Net-(JB8-Pad1)") (class "Default")
      (node (ref "JB8") (pin "1") (pinfunction "1_1") (pintype "passive"))
      (node (ref "R20") (pin "1") (pinfunction "1_1") (pintype "passive"))
      (node (ref "U1") (pin "51") (pinfunction "51_51") (pintype "bidirectional"))
    )
    (net (code "65") (name "Net-(JB8-Pad2)") (class "Default")
      (node (ref "JB8") (pin "2") (pinfunction "2_2") (pintype "passive"))
      (node (ref "R8") (pin "1") (pinfunction "1_1") (pintype "passive"))
    )
    (net (code "66") (name "Net-(JB9-Pad1)") (class "Default")
      (node (ref "JB9") (pin "1") (pinfunction "1_1") (pintype "passive"))
      (node (ref "R29") (pin "1") (pinfunction "1_1") (pintype "passive"))
      (node (ref "U1") (pin "38") (pinfunction "38_38") (pintype "bidirectional"))
    )
    (net (code "67") (name "Net-(JB9-Pad2)") (class "Default")
      (node (ref "JB9") (pin "2") (pinfunction "2_2") (pintype "passive"))
      (node (ref "R9") (pin "1") (pinfunction "1_1") (pintype "passive"))
    )
    (net (code "68") (name "Net-(JB10-Pad1)") (class "Default")
      (node (ref "JB10") (pin "1") (pinfunction "1_1") (pintype "passive"))
      (node (ref "R28") (pin "1") (pinfunction "1_1") (pintype "passive"))
      (node (ref "U1") (pin "34") (pinfunction "34_34") (pintype "bidirectional"))
    )
    (net (code "69") (name "Net-(JB10-Pad2)") (class "Default")
      (node (ref "JB10") (pin "2") (pinfunction "2_2") (pintype "passive"))
      (node (ref "R10") (pin "1") (pinfunction "1_1") (pintype "passive"))
    )
    (net (code "70") (name "Net-(JB11-Pad1)") (class "Default")
      (node (ref "JB11") (pin "1") (pinfunction "1_1") (pintype "passive"))
      (node (ref "R30") (pin "1") (pinfunction "1_1") (pintype "passive"))
      (node (ref "U1") (pin "30") (pinfunction "30_30") (pintype "bidirectional"))
    )
    (net (code "71") (name "Net-(JB11-Pad2)") (class "Default")
      (node (ref "JB11") (pin "2") (pinfunction "2_2") (pintype "passive"))
      (node (ref "R11") (pin "1") (pinfunction "1_1") (pintype "passive"))
    )
    (net (code "72") (name "Net-(JB12-Pad1)") (class "Default")
      (node (ref "JB12") (pin "1") (pinfunction "1_1") (pintype "passive"))
      (node (ref "R31") (pin "1") (pinfunction "1_1") (pintype "passive"))
      (node (ref "U1") (pin "26") (pinfunction "26_26") (pintype "bidirectional"))
    )
    (net (code "73") (name "Net-(JB12-Pad2)") (class "Default")
      (node (ref "JB12") (pin "2") (pinfunction "2_2") (pintype "passive"))
      (node (ref "R12") (pin "1") (pinfunction "1_1") (pintype "passive"))
    )
    (net (code "74") (name "Net-(JB13-Pad1)") (class "Default")
      (node (ref "JB13") (pin "1") (pinfunction "1_1") (pintype "passive"))
      (node (ref "R32") (pin "1") (pinfunction "1_1") (pintype "passive"))
      (node (ref "U1") (pin "22") (pinfunction "22_22") (pintype "bidirectional"))
    )
    (net (code "75") (name "Net-(JB13-Pad2)") (class "Default")
      (node (ref "JB13") (pin "2") (pinfunction "2_2") (pintype "passive"))
      (node (ref "R13") (pin "1") (pinfunction "1_1") (pintype "passive"))
    )
    (net (code "76") (name "Net-(JP1-Pad1)") (class "Default")
      (node (ref "JP1") (pin "1") (pinfunction "1_1") (pintype "passive"))
      (node (ref "JP1") (pin "2") (pinfunction "2_2") (pintype "passive"))
      (node (ref "JP1") (pin "3") (pinfunction "3_3") (pintype "passive"))
      (node (ref "JP1") (pin "4") (pinfunction "4_4") (pintype "passive"))
      (node (ref "JP2") (pin "1") (pinfunction "1_1") (pintype "passive"))
      (node (ref "JP2") (pin "2") (pinfunction "2_2") (pintype "passive"))
      (node (ref "JP2") (pin "3") (pinfunction "3_3") (pintype "passive"))
      (node (ref "JP2") (pin "4") (pinfunction "4_4") (pintype "passive"))
      (node (ref "JP5") (pin "3") (pinfunction "3_3") (pintype "passive"))
      (node (ref "JP5") (pin "4") (pinfunction "4_4") (pintype "passive"))
      (node (ref "R120") (pin "2") (pinfunction "2_2") (pintype "passive"))
      (node (ref "R140") (pin "2") (pinfunction "2_2") (pintype "passive"))
      (node (ref "R160") (pin "2") (pinfunction "2_2") (pintype "passive"))
      (node (ref "R180") (pin "2") (pinfunction "2_2") (pintype "passive"))
      (node (ref "U1") (pin "5V@1") (pinfunction "5V_5V@1") (pintype "bidirectional"))
      (node (ref "U1") (pin "5V@2") (pinfunction "5V_5V@2") (pintype "bidirectional"))
    )
    (net (code "77") (name "Net-(JP_IPHONE-Pad1)") (class "Default")
      (node (ref "JP_IPHONE") (pin "1") (pinfunction "1_1") (pintype "passive"))
      (node (ref "R34") (pin "2") (pinfunction "2_2") (pintype "passive"))
    )
    (net (code "78") (name "Net-(Q1-D)") (class "Default")
      (node (ref "Q1") (pin "3") (pinfunction "D_3") (pintype "bidirectional"))
      (node (ref "R120") (pin "1") (pinfunction "1_1") (pintype "passive"))
      (node (ref "U1") (pin "16") (pinfunction "16(TX2)_16") (pintype "bidirectional"))
    )
    (net (code "79") (name "Net-(Q1-G)") (class "Default")
      (node (ref "16") (pin "2") (pinfunction "2_2") (pintype "passive"))
      (node (ref "Q1") (pin "1") (pinfunction "G_1") (pintype "bidirectional"))
      (node (ref "R110") (pin "2") (pinfunction "2_2") (pintype "passive"))
    )
    (net (code "80") (name "Net-(Q1-S)") (class "Default")
      (node (ref "16") (pin "1") (pinfunction "1_1") (pintype "passive"))
      (node (ref "Q1") (pin "2") (pinfunction "S_2") (pintype "bidirectional"))
      (node (ref "R110") (pin "1") (pinfunction "1_1") (pintype "passive"))
    )
    (net (code "81") (name "Net-(Q2-D)") (class "Default")
      (node (ref "Q2") (pin "3") (pinfunction "D_3") (pintype "bidirectional"))
      (node (ref "R140") (pin "1") (pinfunction "1_1") (pintype "passive"))
      (node (ref "U1") (pin "17") (pinfunction "17(RX2)_17") (pintype "bidirectional"))
    )
    (net (code "82") (name "Net-(Q2-G)") (class "Default")
      (node (ref "17") (pin "2") (pinfunction "2_2") (pintype "passive"))
      (node (ref "Q2") (pin "1") (pinfunction "G_1") (pintype "bidirectional"))
      (node (ref "R130") (pin "2") (pinfunction "2_2") (pintype "passive"))
    )
    (net (code "83") (name "Net-(Q2-S)") (class "Default")
      (node (ref "17") (pin "1") (pinfunction "1_1") (pintype "passive"))
      (node (ref "Q2") (pin "2") (pinfunction "S_2") (pintype "bidirectional"))
      (node (ref "R130") (pin "1") (pinfunction "1_1") (pintype "passive"))
    )
    (net (code "84") (name "Net-(Q3-D)") (class "Default")
      (node (ref "Q3") (pin "3") (pinfunction "D_3") (pintype "bidirectional"))
      (node (ref "R160") (pin "1") (pinfunction "1_1") (pintype "passive"))
      (node (ref "U1") (pin "18") (pinfunction "18(TX1)_18") (pintype "bidirectional"))
    )
    (net (code "85") (name "Net-(Q3-G)") (class "Default")
      (node (ref "JP_IPHONE") (pin "4") (pinfunction "4_4") (pintype "passive"))
      (node (ref "Q3") (pin "1") (pinfunction "G_1") (pintype "bidirectional"))
      (node (ref "Q4") (pin "1") (pinfunction "G_1") (pintype "bidirectional"))
      (node (ref "R150") (pin "2") (pinfunction "2_2") (pintype "passive"))
      (node (ref "R170") (pin "2") (pinfunction "2_2") (pintype "passive"))
    )
    (net (code "86") (name "Net-(Q3-S)") (class "Default")
      (node (ref "JP_IPHONE") (pin "5") (pinfunction "5_5") (pintype "passive"))
      (node (ref "Q3") (pin "2") (pinfunction "S_2") (pintype "bidirectional"))
      (node (ref "R150") (pin "1") (pinfunction "1_1") (pintype "passive"))
    )
    (net (code "87") (name "Net-(Q4-D)") (class "Default")
      (node (ref "Q4") (pin "3") (pinfunction "D_3") (pintype "bidirectional"))
      (node (ref "R180") (pin "1") (pinfunction "1_1") (pintype "passive"))
      (node (ref "U1") (pin "19") (pinfunction "19(RX1)_19") (pintype "bidirectional"))
    )
    (net (code "88") (name "Net-(Q4-S)") (class "Default")
      (node (ref "JP_IPHONE") (pin "6") (pinfunction "6_6") (pintype "passive"))
      (node (ref "Q4") (pin "2") (pinfunction "S_2") (pintype "bidirectional"))
      (node (ref "R170") (pin "1") (pinfunction "1_1") (pintype "passive"))
    )
    (net (code "89") (name "Net-(R-P)") (class "Default")
      (node (ref "R") (pin "1") (pinfunction "P_1") (pintype "passive"))
      (node (ref "U1") (pin "RESET") (pinfunction "RESET_RESET") (pintype "bidirectional"))
    )
    (net (code "90") (name "Net-(R1-Pad2)") (class "Default")
      (node (ref "R1") (pin "2") (pinfunction "2_2") (pintype "passive"))
      (node (ref "U1") (pin "25") (pinfunction "25_25") (pintype "bidirectional"))
    )
    (net (code "91") (name "Net-(R2-Pad2)") (class "Default")
      (node (ref "R2") (pin "2") (pinfunction "2_2") (pintype "passive"))
      (node (ref "U1") (pin "29") (pinfunction "29_29") (pintype "bidirectional"))
    )
    (net (code "92") (name "Net-(R3-Pad2)") (class "Default")
      (node (ref "R3") (pin "2") (pinfunction "2_2") (pintype "passive"))
      (node (ref "U1") (pin "33") (pinfunction "33_33") (pintype "bidirectional"))
    )
    (net (code "93") (name "Net-(R4-Pad2)") (class "Default")
      (node (ref "R4") (pin "2") (pinfunction "2_2") (pintype "passive"))
      (node (ref "U1") (pin "37") (pinfunction "37_37") (pintype "bidirectional"))
    )
    (net (code "94") (name "Net-(R5-Pad2)") (class "Default")
      (node (ref "R5") (pin "2") (pinfunction "2_2") (pintype "passive"))
      (node (ref "U1") (pin "41") (pinfunction "41_41") (pintype "bidirectional"))
    )
    (net (code "95") (name "Net-(R6-Pad2)") (class "Default")
      (node (ref "R6") (pin "2") (pinfunction "2_2") (pintype "passive"))
      (node (ref "U1") (pin "45") (pinfunction "45_45") (pintype "bidirectional"))
    )
    (net (code "96") (name "Net-(R7-Pad2)") (class "Default")
      (node (ref "R7") (pin "2") (pinfunction "2_2") (pintype "passive"))
      (node (ref "U1") (pin "49") (pinfunction "49_49") (pintype "bidirectional"))
    )
    (net (code "97") (name "Net-(R8-Pad2)") (class "Default")
      (node (ref "R8") (pin "2") (pinfunction "2_2") (pintype "passive"))
      (node (ref "U1") (pin "53") (pinfunction "53_53") (pintype "bidirectional"))
    )
    (net (code "98") (name "Net-(R9-Pad2)") (class "Default")
      (node (ref "R9") (pin "2") (pinfunction "2_2") (pintype "passive"))
      (node (ref "U1") (pin "40") (pinfunction "40_40") (pintype "bidirectional"))
    )
    (net (code "99") (name "Net-(R10-Pad2)") (class "Default")
      (node (ref "R10") (pin "2") (pinfunction "2_2") (pintype "passive"))
      (node (ref "U1") (pin "36") (pinfunction "36_36") (pintype "bidirectional"))
    )
    (net (code "100") (name "Net-(R11-Pad2)") (class "Default")
      (node (ref "R11") (pin "2") (pinfunction "2_2") (pintype "passive"))
      (node (ref "U1") (pin "32") (pinfunction "32_32") (pintype "bidirectional"))
    )
    (net (code "101") (name "Net-(R12-Pad2)") (class "Default")
      (node (ref "R12") (pin "2") (pinfunction "2_2") (pintype "passive"))
      (node (ref "U1") (pin "28") (pinfunction "28_28") (pintype "bidirectional"))
    )
    (net (code "102") (name "Net-(R13-Pad2)") (class "Default")
      (node (ref "R13") (pin "2") (pinfunction "2_2") (pintype "passive"))
      (node (ref "U1") (pin "24") (pinfunction "24_24") (pintype "bidirectional"))
    )
    (net (code "103") (name "Net-(R19-Pad2)") (class "Default")
      (node (ref "R19") (pin "2") (pinfunction "2_2") (pintype "passive"))
      (node (ref "R35") (pin "2") (pinfunction "2_2") (pintype "passive"))
      (node (ref "U1") (pin "52") (pinfunction "52_52") (pintype "bidirectional"))
    )
    (net (code "104") (name "Net-(T1-B)") (class "Default")
      (node (ref "R19") (pin "1") (pinfunction "1_1") (pintype "passive"))
      (node (ref "R35") (pin "1") (pinfunction "1_1") (pintype "passive"))
      (node (ref "T1") (pin "1") (pinfunction "B_1") (pintype "passive"))
    )
    (net (code "105") (name "Net-(T1-C)") (class "Default")
      (node (ref "T1") (pin "3") (pinfunction "C_3") (pintype "passive"))
      (node (ref "U$1") (pin "1") (pinfunction "ON/OFF_1") (pintype "bidirectional"))
    )
    (net (code "106") (name "Net-(U$1-VADJ)") (class "Default")
      (node (ref "R33") (pin "2") (pinfunction "2_2") (pintype "passive"))
      (node (ref "U$1") (pin "7") (pinfunction "VADJ_7") (pintype "bidirectional"))
    )
  )
)
